# SCH_R-2R-Ladder_2024-10-07.net
KiCad netlist of a schematic drawn in EasyEDA
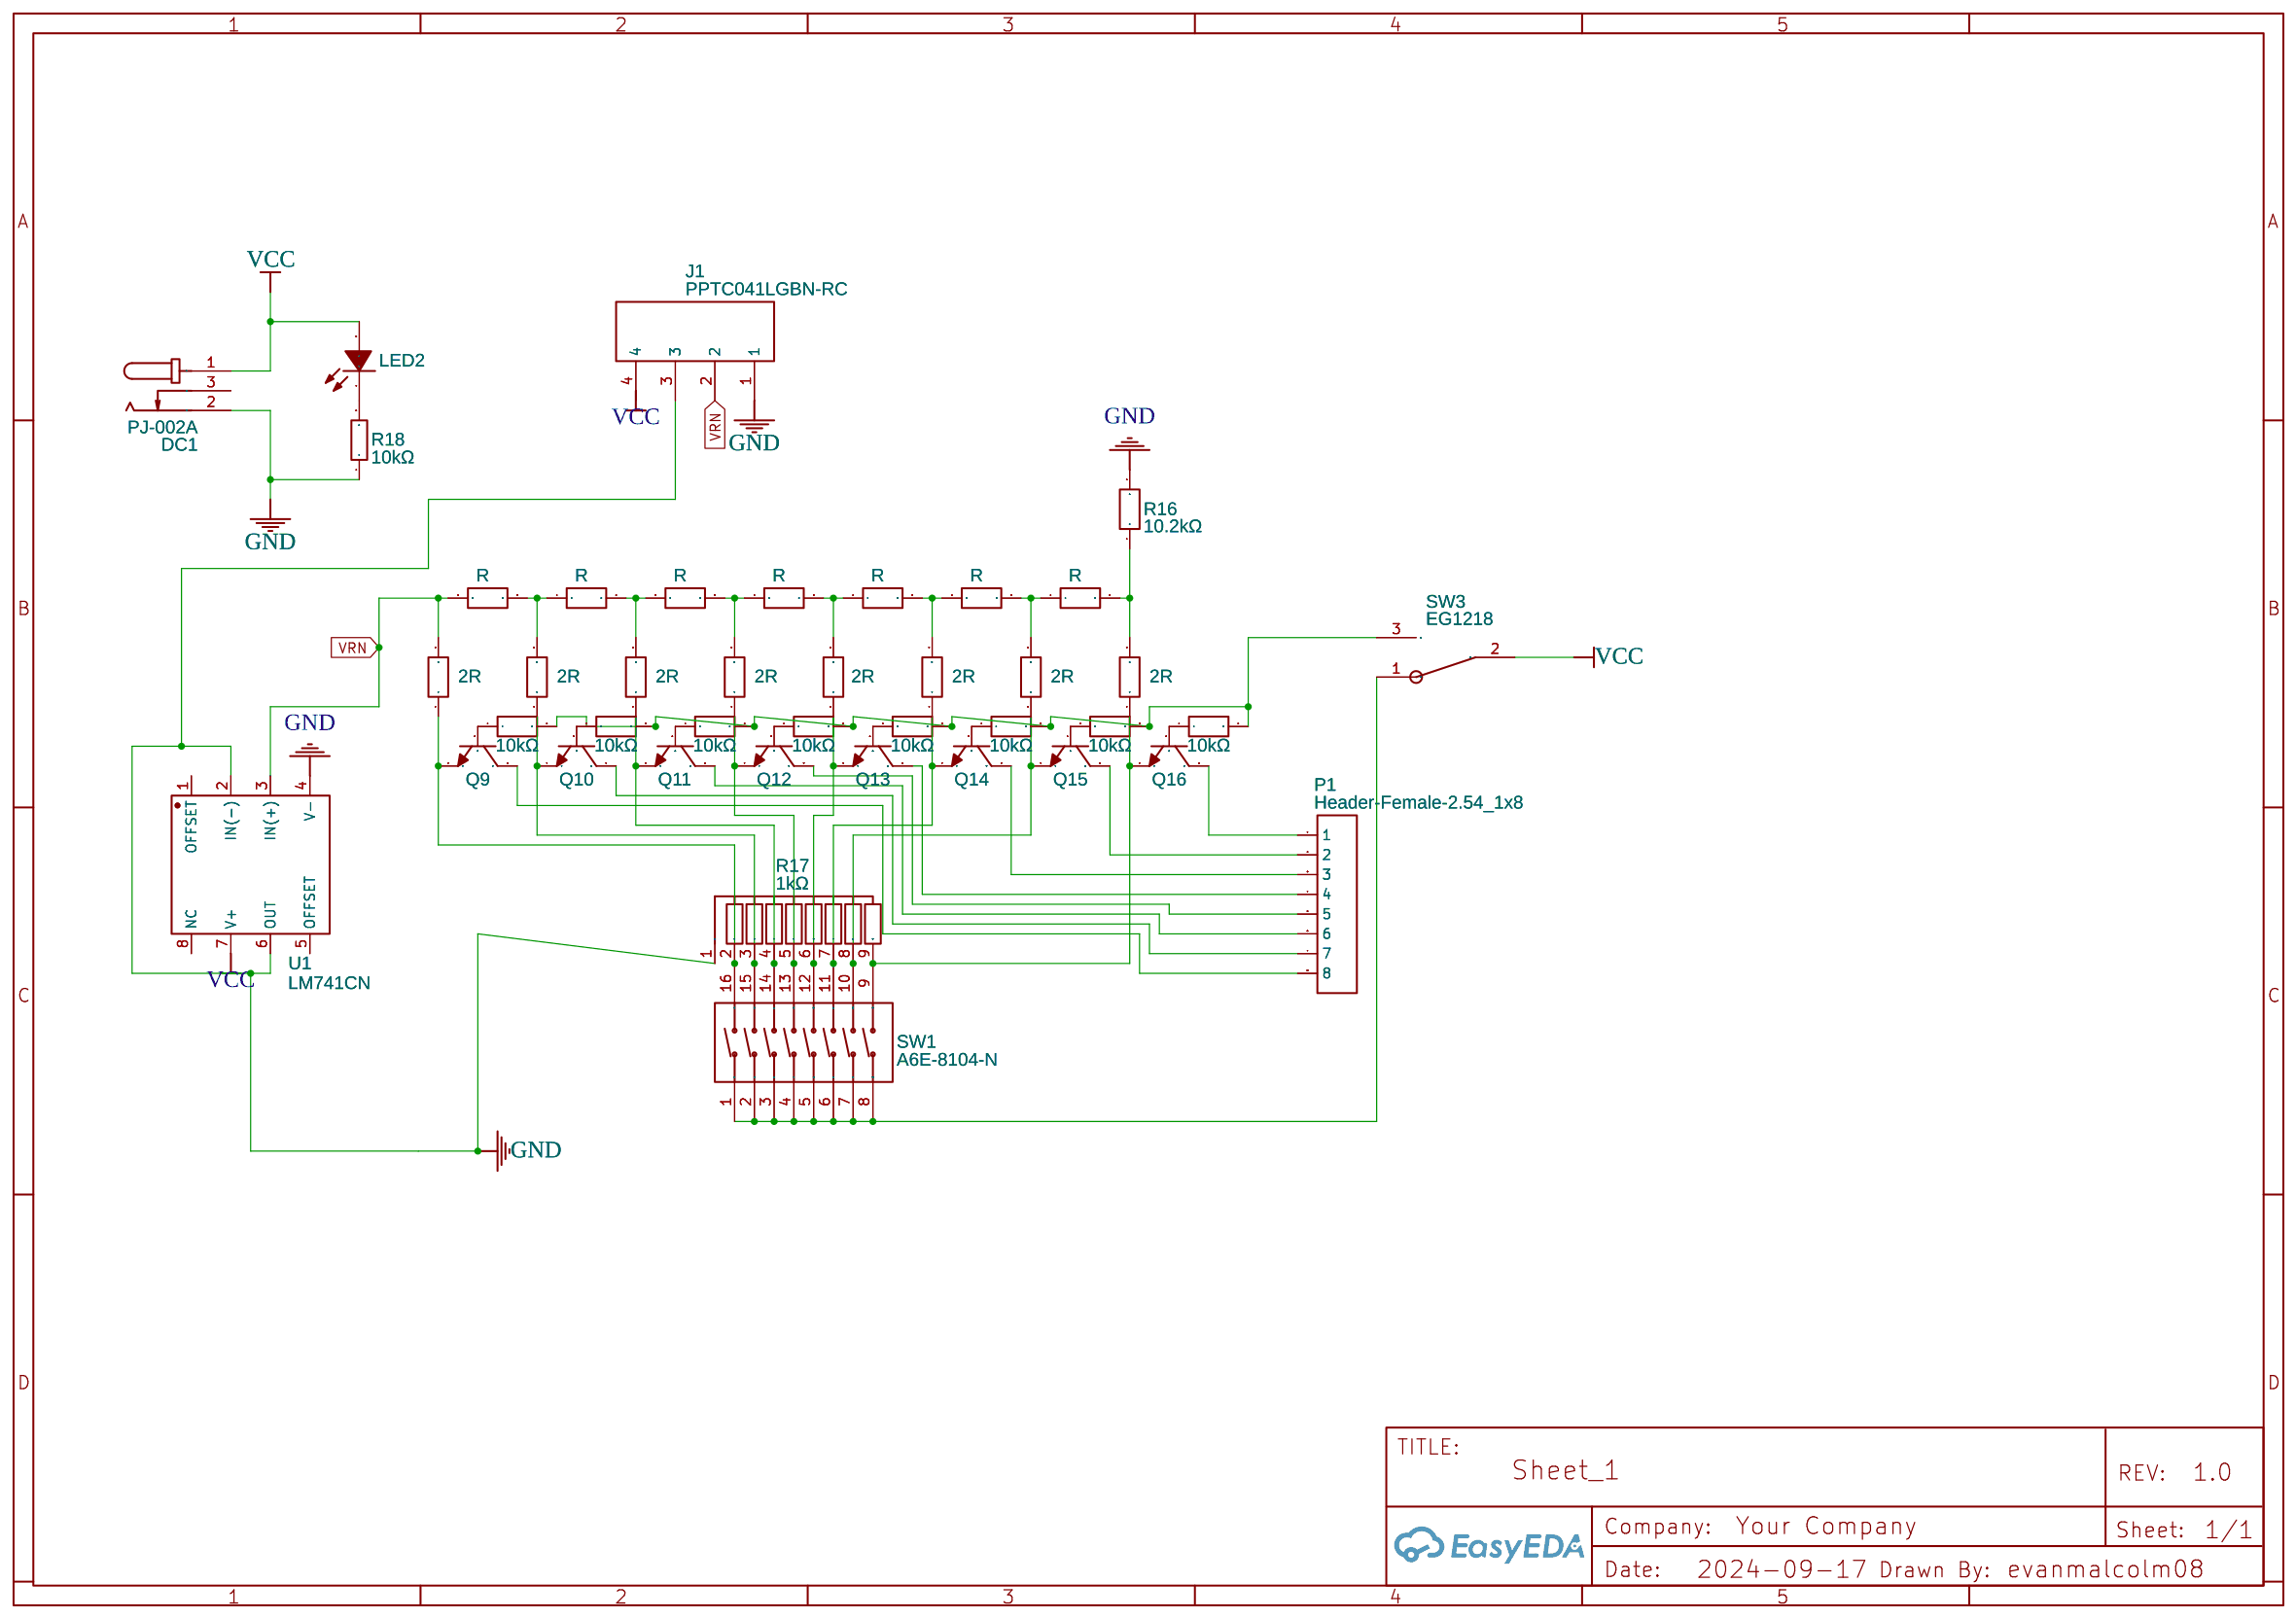
[diagram p0: schematic sheet]

(export (version "E")
  (design (tool "Eeschema 10.0.6"))
  (components
    (comp (ref "DC1")
      (value "PJ-002A")
      (fields (field (name "Manufacturer") "CUI"))
      (libsource (lib "") (part "PJ-002A"))
    )
    (comp (ref "J1") (value "PPTC041LGBN-RC") (libsource (lib "") (part "PPTC041LGBN-RC")))
    (comp (ref "LED2")
      (value "LTST-C150TBKT")
      (fields (field (name "Manufacturer") "LITEON(光宝)"))
      (libsource (lib "") (part "LTST-C150TBKT"))
    )
    (comp (ref "P1")
      (value "Header-Female-2.54_1x8")
      (fields (field (name "Manufacturer Part") "2.54-1*8P母环保") (field (name "Manufacturer") "BOOMELE(博穆精密)"))
      (libsource (lib "") (part "Header-Female-2.54_1x8"))
    )
    (comp (ref "Q9")
      (value "2N3904TF")
      (fields (field (name "Manufacturer") "onsemi(安森美)"))
      (libsource (lib "") (part "2N3904TF"))
    )
    (comp (ref "Q10")
      (value "2N3904TF")
      (fields (field (name "Manufacturer") "onsemi(安森美)"))
      (libsource (lib "") (part "2N3904TF"))
    )
    (comp (ref "Q11")
      (value "2N3904TF")
      (fields (field (name "Manufacturer") "onsemi(安森美)"))
      (libsource (lib "") (part "2N3904TF"))
    )
    (comp (ref "Q12")
      (value "2N3904TF")
      (fields (field (name "Manufacturer") "onsemi(安森美)"))
      (libsource (lib "") (part "2N3904TF"))
    )
    (comp (ref "Q13")
      (value "2N3904TF")
      (fields (field (name "Manufacturer") "onsemi(安森美)"))
      (libsource (lib "") (part "2N3904TF"))
    )
    (comp (ref "Q14")
      (value "2N3904TF")
      (fields (field (name "Manufacturer") "onsemi(安森美)"))
      (libsource (lib "") (part "2N3904TF"))
    )
    (comp (ref "Q15")
      (value "2N3904TF")
      (fields (field (name "Manufacturer") "onsemi(安森美)"))
      (libsource (lib "") (part "2N3904TF"))
    )
    (comp (ref "Q16")
      (value "2N3904TF")
      (fields (field (name "Manufacturer") "onsemi(安森美)"))
      (libsource (lib "") (part "2N3904TF"))
    )
    (comp (ref "R1")
      (value "R")
      (fields
        (field (name "Manufacturer Part") "CF14JT10K0")
        (field (name "Manufacturer") "SEI(Stackpole Electronics Inc.)")
      )
      (libsource (lib "") (part "CF14JT10K0"))
    )
    (comp (ref "R2")
      (value "R")
      (fields
        (field (name "Manufacturer Part") "CF14JT10K0")
        (field (name "Manufacturer") "SEI(Stackpole Electronics Inc.)")
      )
      (libsource (lib "") (part "CF14JT10K0"))
    )
    (comp (ref "R3")
      (value "R")
      (fields
        (field (name "Manufacturer Part") "CF14JT10K0")
        (field (name "Manufacturer") "SEI(Stackpole Electronics Inc.)")
      )
      (libsource (lib "") (part "CF14JT10K0"))
    )
    (comp (ref "R4")
      (value "R")
      (fields
        (field (name "Manufacturer Part") "CF14JT10K0")
        (field (name "Manufacturer") "SEI(Stackpole Electronics Inc.)")
      )
      (libsource (lib "") (part "CF14JT10K0"))
    )
    (comp (ref "R5")
      (value "R")
      (fields
        (field (name "Manufacturer Part") "CF14JT10K0")
        (field (name "Manufacturer") "SEI(Stackpole Electronics Inc.)")
      )
      (libsource (lib "") (part "CF14JT10K0"))
    )
    (comp (ref "R6")
      (value "R")
      (fields
        (field (name "Manufacturer Part") "CF14JT10K0")
        (field (name "Manufacturer") "SEI(Stackpole Electronics Inc.)")
      )
      (libsource (lib "") (part "CF14JT10K0"))
    )
    (comp (ref "R7")
      (value "R")
      (fields
        (field (name "Manufacturer Part") "CF14JT10K0")
        (field (name "Manufacturer") "SEI(Stackpole Electronics Inc.)")
      )
      (libsource (lib "") (part "CF14JT10K0"))
    )
    (comp (ref "R8")
      (value "2R")
      (fields
        (field (name "Manufacturer Part") "CF14JT10K0")
        (field (name "Manufacturer") "SEI(Stackpole Electronics Inc.)")
      )
      (libsource (lib "") (part "CF14JT10K0_1"))
    )
    (comp (ref "R9")
      (value "2R")
      (fields
        (field (name "Manufacturer Part") "CF14JT10K0")
        (field (name "Manufacturer") "SEI(Stackpole Electronics Inc.)")
      )
      (libsource (lib "") (part "CF14JT10K0_1"))
    )
    (comp (ref "R10")
      (value "2R")
      (fields
        (field (name "Manufacturer Part") "CF14JT10K0")
        (field (name "Manufacturer") "SEI(Stackpole Electronics Inc.)")
      )
      (libsource (lib "") (part "CF14JT10K0_1"))
    )
    (comp (ref "R11")
      (value "2R")
      (fields
        (field (name "Manufacturer Part") "CF14JT10K0")
        (field (name "Manufacturer") "SEI(Stackpole Electronics Inc.)")
      )
      (libsource (lib "") (part "CF14JT10K0_1"))
    )
    (comp (ref "R12")
      (value "2R")
      (fields
        (field (name "Manufacturer Part") "CF14JT10K0")
        (field (name "Manufacturer") "SEI(Stackpole Electronics Inc.)")
      )
      (libsource (lib "") (part "CF14JT10K0_1"))
    )
    (comp (ref "R13")
      (value "2R")
      (fields
        (field (name "Manufacturer Part") "CF14JT10K0")
        (field (name "Manufacturer") "SEI(Stackpole Electronics Inc.)")
      )
      (libsource (lib "") (part "CF14JT10K0_1"))
    )
    (comp (ref "R14")
      (value "2R")
      (fields
        (field (name "Manufacturer Part") "CF14JT10K0")
        (field (name "Manufacturer") "SEI(Stackpole Electronics Inc.)")
      )
      (libsource (lib "") (part "CF14JT10K0_1"))
    )
    (comp (ref "R15")
      (value "2R")
      (fields
        (field (name "Manufacturer Part") "CF14JT10K0")
        (field (name "Manufacturer") "SEI(Stackpole Electronics Inc.)")
      )
      (libsource (lib "") (part "CF14JT10K0_1"))
    )
    (comp (ref "R16")
      (value "10.2kΩ")
      (fields
        (field (name "Manufacturer Part") "CF14JT10K0")
        (field (name "Manufacturer") "SEI(Stackpole Electronics Inc.)")
      )
      (libsource (lib "") (part "CF14JT10K0_1"))
    )
    (comp (ref "R17")
      (value "1kΩ")
      (fields (field (name "Manufacturer Part") "4609X-101-102LF") (field (name "Manufacturer") "BOURNS"))
      (libsource (lib "") (part "4609X-101-102LF"))
    )
    (comp (ref "R18")
      (value "10kΩ")
      (fields (field (name "Manufacturer Part") "CR1206-FX-1002ELF") (field (name "Manufacturer") "BOURNS"))
      (libsource (lib "") (part "CR1206-FX-1002ELF"))
    )
    (comp (ref "R27")
      (value "10kΩ")
      (fields
        (field (name "Manufacturer Part") "CF14JT10K0")
        (field (name "Manufacturer") "SEI(Stackpole Electronics Inc.)")
      )
      (libsource (lib "") (part "CF14JT10K0"))
    )
    (comp (ref "R28")
      (value "10kΩ")
      (fields
        (field (name "Manufacturer Part") "CF14JT10K0")
        (field (name "Manufacturer") "SEI(Stackpole Electronics Inc.)")
      )
      (libsource (lib "") (part "CF14JT10K0"))
    )
    (comp (ref "R29")
      (value "10kΩ")
      (fields
        (field (name "Manufacturer Part") "CF14JT10K0")
        (field (name "Manufacturer") "SEI(Stackpole Electronics Inc.)")
      )
      (libsource (lib "") (part "CF14JT10K0"))
    )
    (comp (ref "R30")
      (value "10kΩ")
      (fields
        (field (name "Manufacturer Part") "CF14JT10K0")
        (field (name "Manufacturer") "SEI(Stackpole Electronics Inc.)")
      )
      (libsource (lib "") (part "CF14JT10K0"))
    )
    (comp (ref "R31")
      (value "10kΩ")
      (fields
        (field (name "Manufacturer Part") "CF14JT10K0")
        (field (name "Manufacturer") "SEI(Stackpole Electronics Inc.)")
      )
      (libsource (lib "") (part "CF14JT10K0"))
    )
    (comp (ref "R32")
      (value "10kΩ")
      (fields
        (field (name "Manufacturer Part") "CF14JT10K0")
        (field (name "Manufacturer") "SEI(Stackpole Electronics Inc.)")
      )
      (libsource (lib "") (part "CF14JT10K0"))
    )
    (comp (ref "R33")
      (value "10kΩ")
      (fields
        (field (name "Manufacturer Part") "CF14JT10K0")
        (field (name "Manufacturer") "SEI(Stackpole Electronics Inc.)")
      )
      (libsource (lib "") (part "CF14JT10K0"))
    )
    (comp (ref "R34")
      (value "10kΩ")
      (fields
        (field (name "Manufacturer Part") "CF14JT10K0")
        (field (name "Manufacturer") "SEI(Stackpole Electronics Inc.)")
      )
      (libsource (lib "") (part "CF14JT10K0"))
    )
    (comp (ref "SW1")
      (value "A6E-8104-N")
      (fields (field (name "Manufacturer") "OMRON(欧姆龙)"))
      (libsource (lib "") (part "A6E-8104-N"))
    )
    (comp (ref "SW3")
      (value "EG1218")
      (fields (field (name "Manufacturer") "E-Switch"))
      (libsource (lib "") (part "EG1218"))
    )
    (comp (ref "U1")
      (value "LM741CN")
      (fields (field (name "Manufacturer Part") "LM741CN/NOPB") (field (name "Manufacturer") "TI(德州仪器)"))
      (libsource (lib "") (part "LM741CN"))
    )
  )
  (nets
    (net (code "1") (name "GND") (class "Default")
      (node (ref "DC1") (pin "2") (pinfunction "2_2") (pintype "unspecified"))
      (node (ref "J1") (pin "1") (pinfunction "1_1") (pintype "unspecified"))
      (node (ref "J1") (pin "3") (pinfunction "3_3") (pintype "unspecified"))
      (node (ref "R16") (pin "2") (pinfunction "2_2") (pintype "unspecified"))
      (node (ref "R17") (pin "1") (pinfunction "1_1") (pintype "unspecified"))
      (node (ref "R18") (pin "1") (pinfunction "1_1") (pintype "unspecified"))
      (node (ref "U1") (pin "2") (pinfunction "IN(-)_2") (pintype "unspecified"))
      (node (ref "U1") (pin "4") (pinfunction "V-_4") (pintype "unspecified"))
      (node (ref "U1") (pin "6") (pinfunction "OUT_6") (pintype "unspecified"))
    )
    (net (code "2") (name "Net-(LED2-K)") (class "Default")
      (node (ref "LED2") (pin "1") (pinfunction "K_1") (pintype "unspecified"))
      (node (ref "R18") (pin "2") (pinfunction "2_2") (pintype "unspecified"))
    )
    (net (code "3") (name "Net-(Q9-B)") (class "Default")
      (node (ref "Q9") (pin "2") (pinfunction "B_2") (pintype "input"))
      (node (ref "R34") (pin "1") (pinfunction "1_1") (pintype "unspecified"))
    )
    (net (code "4") (name "Net-(Q9-C)") (class "Default")
      (node (ref "P1") (pin "8") (pinfunction "8_8") (pintype "input"))
      (node (ref "Q9") (pin "3") (pinfunction "C_3") (pintype "input"))
    )
    (net (code "5") (name "Net-(Q9-E)") (class "Default")
      (node (ref "Q9") (pin "1") (pinfunction "E_1") (pintype "input"))
      (node (ref "R17") (pin "2") (pinfunction "2_2") (pintype "unspecified"))
      (node (ref "R8") (pin "1") (pinfunction "1_1") (pintype "unspecified"))
      (node (ref "SW1") (pin "16") (pinfunction "16_16") (pintype "unspecified"))
    )
    (net (code "6") (name "Net-(Q10-B)") (class "Default")
      (node (ref "Q10") (pin "2") (pinfunction "B_2") (pintype "input"))
      (node (ref "R33") (pin "1") (pinfunction "1_1") (pintype "unspecified"))
    )
    (net (code "7") (name "Net-(Q10-C)") (class "Default")
      (node (ref "P1") (pin "7") (pinfunction "7_7") (pintype "input"))
      (node (ref "Q10") (pin "3") (pinfunction "C_3") (pintype "input"))
    )
    (net (code "8") (name "Net-(Q10-E)") (class "Default")
      (node (ref "Q10") (pin "1") (pinfunction "E_1") (pintype "input"))
      (node (ref "R17") (pin "3") (pinfunction "3_3") (pintype "unspecified"))
      (node (ref "R9") (pin "1") (pinfunction "1_1") (pintype "unspecified"))
      (node (ref "SW1") (pin "15") (pinfunction "15_15") (pintype "unspecified"))
    )
    (net (code "9") (name "Net-(Q11-B)") (class "Default")
      (node (ref "Q11") (pin "2") (pinfunction "B_2") (pintype "input"))
      (node (ref "R32") (pin "1") (pinfunction "1_1") (pintype "unspecified"))
    )
    (net (code "10") (name "Net-(Q11-C)") (class "Default")
      (node (ref "P1") (pin "6") (pinfunction "6_6") (pintype "input"))
      (node (ref "Q11") (pin "3") (pinfunction "C_3") (pintype "input"))
    )
    (net (code "11") (name "Net-(Q11-E)") (class "Default")
      (node (ref "Q11") (pin "1") (pinfunction "E_1") (pintype "input"))
      (node (ref "R10") (pin "1") (pinfunction "1_1") (pintype "unspecified"))
      (node (ref "R17") (pin "4") (pinfunction "4_4") (pintype "unspecified"))
      (node (ref "SW1") (pin "14") (pinfunction "14_14") (pintype "unspecified"))
    )
    (net (code "12") (name "Net-(Q12-B)") (class "Default")
      (node (ref "Q12") (pin "2") (pinfunction "B_2") (pintype "input"))
      (node (ref "R31") (pin "1") (pinfunction "1_1") (pintype "unspecified"))
    )
    (net (code "13") (name "Net-(Q12-C)") (class "Default")
      (node (ref "P1") (pin "5") (pinfunction "5_5") (pintype "input"))
      (node (ref "Q12") (pin "3") (pinfunction "C_3") (pintype "input"))
    )
    (net (code "14") (name "Net-(Q12-E)") (class "Default")
      (node (ref "Q12") (pin "1") (pinfunction "E_1") (pintype "input"))
      (node (ref "R11") (pin "1") (pinfunction "1_1") (pintype "unspecified"))
      (node (ref "R17") (pin "5") (pinfunction "5_5") (pintype "unspecified"))
      (node (ref "SW1") (pin "13") (pinfunction "13_13") (pintype "unspecified"))
    )
    (net (code "15") (name "Net-(Q13-B)") (class "Default")
      (node (ref "Q13") (pin "2") (pinfunction "B_2") (pintype "input"))
      (node (ref "R30") (pin "1") (pinfunction "1_1") (pintype "unspecified"))
    )
    (net (code "16") (name "Net-(Q13-C)") (class "Default")
      (node (ref "P1") (pin "4") (pinfunction "4_4") (pintype "input"))
      (node (ref "Q13") (pin "3") (pinfunction "C_3") (pintype "input"))
    )
    (net (code "17") (name "Net-(Q13-E)") (class "Default")
      (node (ref "Q13") (pin "1") (pinfunction "E_1") (pintype "input"))
      (node (ref "R12") (pin "1") (pinfunction "1_1") (pintype "unspecified"))
      (node (ref "R17") (pin "6") (pinfunction "6_6") (pintype "unspecified"))
      (node (ref "SW1") (pin "12") (pinfunction "12_12") (pintype "unspecified"))
    )
    (net (code "18") (name "Net-(Q14-B)") (class "Default")
      (node (ref "Q14") (pin "2") (pinfunction "B_2") (pintype "input"))
      (node (ref "R29") (pin "1") (pinfunction "1_1") (pintype "unspecified"))
    )
    (net (code "19") (name "Net-(Q14-C)") (class "Default")
      (node (ref "P1") (pin "3") (pinfunction "3_3") (pintype "input"))
      (node (ref "Q14") (pin "3") (pinfunction "C_3") (pintype "input"))
    )
    (net (code "20") (name "Net-(Q14-E)") (class "Default")
      (node (ref "Q14") (pin "1") (pinfunction "E_1") (pintype "input"))
      (node (ref "R13") (pin "1") (pinfunction "1_1") (pintype "unspecified"))
      (node (ref "R17") (pin "7") (pinfunction "7_7") (pintype "unspecified"))
      (node (ref "SW1") (pin "11") (pinfunction "11_11") (pintype "unspecified"))
    )
    (net (code "21") (name "Net-(Q15-B)") (class "Default")
      (node (ref "Q15") (pin "2") (pinfunction "B_2") (pintype "input"))
      (node (ref "R28") (pin "1") (pinfunction "1_1") (pintype "unspecified"))
    )
    (net (code "22") (name "Net-(Q15-C)") (class "Default")
      (node (ref "P1") (pin "2") (pinfunction "2_2") (pintype "input"))
      (node (ref "Q15") (pin "3") (pinfunction "C_3") (pintype "input"))
    )
    (net (code "23") (name "Net-(Q15-E)") (class "Default")
      (node (ref "Q15") (pin "1") (pinfunction "E_1") (pintype "input"))
      (node (ref "R14") (pin "1") (pinfunction "1_1") (pintype "unspecified"))
      (node (ref "R17") (pin "8") (pinfunction "8_8") (pintype "unspecified"))
      (node (ref "SW1") (pin "10") (pinfunction "10_10") (pintype "unspecified"))
    )
    (net (code "24") (name "Net-(Q16-B)") (class "Default")
      (node (ref "Q16") (pin "2") (pinfunction "B_2") (pintype "input"))
      (node (ref "R27") (pin "1") (pinfunction "1_1") (pintype "unspecified"))
    )
    (net (code "25") (name "Net-(Q16-C)") (class "Default")
      (node (ref "P1") (pin "1") (pinfunction "1_1") (pintype "input"))
      (node (ref "Q16") (pin "3") (pinfunction "C_3") (pintype "input"))
    )
    (net (code "26") (name "Net-(Q16-E)") (class "Default")
      (node (ref "Q16") (pin "1") (pinfunction "E_1") (pintype "input"))
      (node (ref "R15") (pin "1") (pinfunction "1_1") (pintype "unspecified"))
      (node (ref "R17") (pin "9") (pinfunction "9_9") (pintype "unspecified"))
      (node (ref "SW1") (pin "9") (pinfunction "9_9") (pintype "unspecified"))
    )
    (net (code "27") (name "Net-(R1-Pad2)") (class "Default")
      (node (ref "R1") (pin "2") (pinfunction "2_2") (pintype "unspecified"))
      (node (ref "R2") (pin "1") (pinfunction "1_1") (pintype "unspecified"))
      (node (ref "R9") (pin "2") (pinfunction "2_2") (pintype "unspecified"))
    )
    (net (code "28") (name "Net-(R10-Pad2)") (class "Default")
      (node (ref "R10") (pin "2") (pinfunction "2_2") (pintype "unspecified"))
      (node (ref "R2") (pin "2") (pinfunction "2_2") (pintype "unspecified"))
      (node (ref "R3") (pin "1") (pinfunction "1_1") (pintype "unspecified"))
    )
    (net (code "29") (name "Net-(R11-Pad2)") (class "Default")
      (node (ref "R11") (pin "2") (pinfunction "2_2") (pintype "unspecified"))
      (node (ref "R3") (pin "2") (pinfunction "2_2") (pintype "unspecified"))
      (node (ref "R4") (pin "1") (pinfunction "1_1") (pintype "unspecified"))
    )
    (net (code "30") (name "Net-(R12-Pad2)") (class "Default")
      (node (ref "R12") (pin "2") (pinfunction "2_2") (pintype "unspecified"))
      (node (ref "R4") (pin "2") (pinfunction "2_2") (pintype "unspecified"))
      (node (ref "R5") (pin "1") (pinfunction "1_1") (pintype "unspecified"))
    )
    (net (code "31") (name "Net-(R13-Pad2)") (class "Default")
      (node (ref "R13") (pin "2") (pinfunction "2_2") (pintype "unspecified"))
      (node (ref "R5") (pin "2") (pinfunction "2_2") (pintype "unspecified"))
      (node (ref "R6") (pin "1") (pinfunction "1_1") (pintype "unspecified"))
    )
    (net (code "32") (name "Net-(R14-Pad2)") (class "Default")
      (node (ref "R14") (pin "2") (pinfunction "2_2") (pintype "unspecified"))
      (node (ref "R6") (pin "2") (pinfunction "2_2") (pintype "unspecified"))
      (node (ref "R7") (pin "1") (pinfunction "1_1") (pintype "unspecified"))
    )
    (net (code "33") (name "Net-(R15-Pad2)") (class "Default")
      (node (ref "R15") (pin "2") (pinfunction "2_2") (pintype "unspecified"))
      (node (ref "R16") (pin "1") (pinfunction "1_1") (pintype "unspecified"))
      (node (ref "R7") (pin "2") (pinfunction "2_2") (pintype "unspecified"))
    )
    (net (code "34") (name "Net-(R27-Pad2)") (class "Default")
      (node (ref "R27") (pin "2") (pinfunction "2_2") (pintype "unspecified"))
      (node (ref "R28") (pin "2") (pinfunction "2_2") (pintype "unspecified"))
      (node (ref "R29") (pin "2") (pinfunction "2_2") (pintype "unspecified"))
      (node (ref "R30") (pin "2") (pinfunction "2_2") (pintype "unspecified"))
      (node (ref "R31") (pin "2") (pinfunction "2_2") (pintype "unspecified"))
      (node (ref "R32") (pin "2") (pinfunction "2_2") (pintype "unspecified"))
      (node (ref "R33") (pin "2") (pinfunction "2_2") (pintype "unspecified"))
      (node (ref "R34") (pin "2") (pinfunction "2_2") (pintype "unspecified"))
      (node (ref "SW3") (pin "3") (pinfunction "3_3") (pintype "input"))
    )
    (net (code "35") (name "Net-(SW1-Pad1)") (class "Default")
      (node (ref "SW1") (pin "1") (pinfunction "1_1") (pintype "unspecified"))
      (node (ref "SW1") (pin "2") (pinfunction "2_2") (pintype "unspecified"))
      (node (ref "SW1") (pin "3") (pinfunction "3_3") (pintype "unspecified"))
      (node (ref "SW1") (pin "4") (pinfunction "4_4") (pintype "unspecified"))
      (node (ref "SW1") (pin "5") (pinfunction "5_5") (pintype "unspecified"))
      (node (ref "SW1") (pin "6") (pinfunction "6_6") (pintype "unspecified"))
      (node (ref "SW1") (pin "7") (pinfunction "7_7") (pintype "unspecified"))
      (node (ref "SW1") (pin "8") (pinfunction "8_8") (pintype "unspecified"))
      (node (ref "SW3") (pin "1") (pinfunction "1_1") (pintype "input"))
    )
    (net (code "36") (name "VCC") (class "Default")
      (node (ref "DC1") (pin "1") (pinfunction "1_1") (pintype "unspecified"))
      (node (ref "LED2") (pin "2") (pinfunction "A_2") (pintype "unspecified"))
      (node (ref "SW3") (pin "2") (pinfunction "2_2") (pintype "input"))
      (node (ref "U1") (pin "7") (pinfunction "V+_7") (pintype "unspecified"))
    )
    (net (code "37") (name "VRN") (class "Default")
      (node (ref "J1") (pin "2") (pinfunction "2_2") (pintype "unspecified"))
      (node (ref "R1") (pin "1") (pinfunction "1_1") (pintype "unspecified"))
      (node (ref "R8") (pin "2") (pinfunction "2_2") (pintype "unspecified"))
      (node (ref "U1") (pin "3") (pinfunction "IN(+)_3") (pintype "unspecified"))
    )
    (net (code "38") (name "unconnected-(DC1-Pad3)") (class "Default")
      (node (ref "DC1") (pin "3") (pinfunction "3_3") (pintype "unspecified"))
    )
    (net (code "39") (name "unconnected-(J1-Pad4)") (class "Default")
      (node (ref "J1") (pin "4") (pinfunction "4_4") (pintype "unspecified"))
    )
    (net (code "40") (name "unconnected-(U1-NC-Pad8)") (class "Default")
      (node (ref "U1") (pin "8") (pinfunction "NC_8") (pintype "unspecified"))
    )
    (net (code "41") (name "unconnected-(U1-OFFSET-Pad1)") (class "Default")
      (node (ref "U1") (pin "1") (pinfunction "OFFSET_1") (pintype "unspecified"))
    )
    (net (code "42") (name "unconnected-(U1-OFFSET-Pad5)") (class "Default")
      (node (ref "U1") (pin "5") (pinfunction "OFFSET_5") (pintype "unspecified"))
    )
  )
)
